# VoedingSCH.net
KiCad netlist of a schematic drawn in Altium Designer
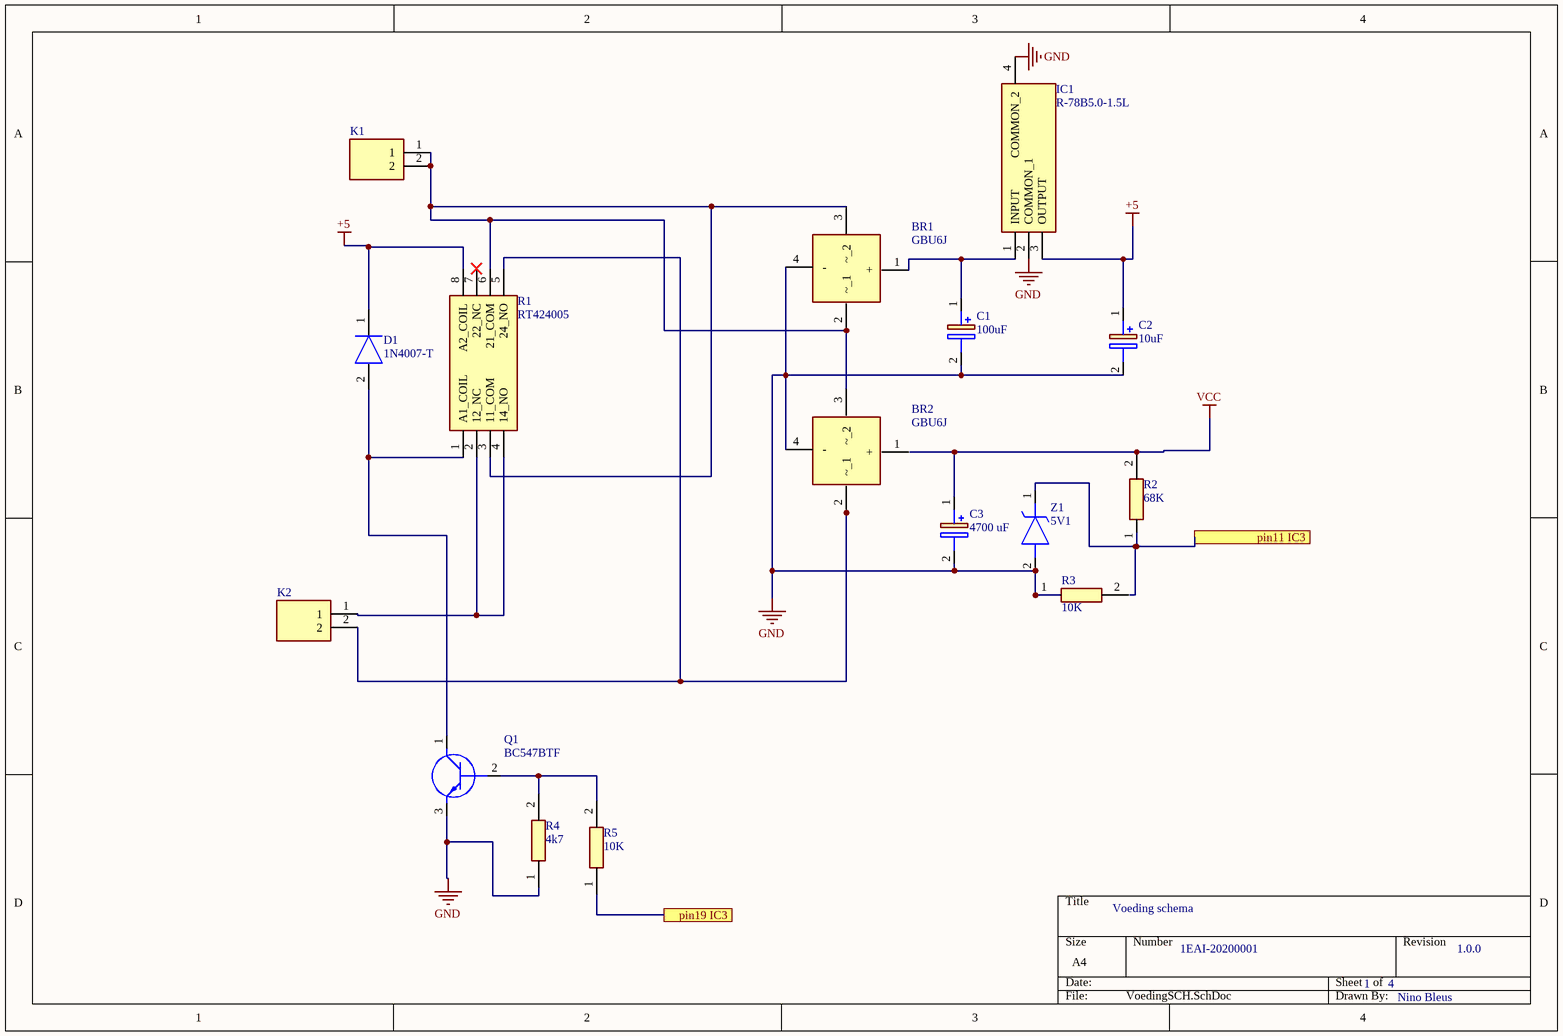
[diagram p0: VoedingSCH.SchDoc]

(export (version "E")
  (design (tool "Eeschema 10.0.6"))
  (components
    (comp (ref "BR1")
      (value "GBU6J")
      (footprint "SamacSys:GBU6J")
      (description "Bridge Rectifier")
      (libsource (lib "Schlib_soldeerbout") (part "GBU6J"))
    )
    (comp (ref "BR2")
      (value "GBU6J")
      (footprint "SamacSys:GBU6J")
      (description "Bridge Rectifier")
      (libsource (lib "Schlib_soldeerbout") (part "GBU6J"))
    )
    (comp (ref "C1")
      (value "100uF")
      (footprint "SamacSys:CAPPRD350W60D800H1250")
      (description "Capacitor Polarised")
      (fields (field (name "MANUFACTURER_PART_NUMBER") "ESK107M050AG3EA"))
      (libsource (lib "*") (part "ESK107M050AG3EA"))
    )
    (comp (ref "C2")
      (value "10uF")
      (footprint "SamacSys:CAPPRD250W45D630H850")
      (description "Capacitor Polarised")
      (fields (field (name "MANUFACTURER_PART_NUMBER") "ESS106M050AE2AA"))
      (libsource (lib "Schlib_soldeerbout") (part "10uF Capaciteit"))
    )
    (comp (ref "C3")
      (value "4700 uF")
      (footprint "SamacSys:CAPPRD1000W80D2200H3700")
      (description "Capacitor Polarised")
      (fields
        (field (name "MOUSER2 PART NUMBER") "80-ESK478M050AQ3AA")
        (field (name "MANUFACTURER_PART_NUMBER") "ESK478M050AQ3AA")
      )
      (libsource (lib "Schlib_soldeerbout") (part "4700 uF capaciteit"))
    )
    (comp (ref "D1")
      (value "1N4007-T")
      (footprint "SamacSys:DIOAD1408W86L464D236")
      (description "Diode")
      (fields (field (name "MOUSER2 PART NUMBER") "583-1N4007-T"))
      (libsource (lib "Schlib_soldeerbout") (part "1N4007-T"))
    )
    (comp (ref "IC1")
      (value "R-78B5.0-1.5L")
      (footprint "SamacSys:TL78005CKTTR")
      (description "Integrated Circuit")
      (fields (field (name "MANUFACTURER_PART_NUMBER") "TL780-05CKTTR"))
      (libsource (lib "*") (part "TL780-05CKTTR"))
    )
    (comp (ref "K1")
      (value "printkroonconnector")
      (footprint "SamacSys:1729128")
      (description "Connector")
      (fields (field (name "MANUFACTURER_PART_NUMBER") "1729128"))
      (libsource (lib "Schlib_soldeerbout") (part "printkroonconnector"))
    )
    (comp (ref "K2")
      (value "printkroonconnector")
      (footprint "SamacSys:1729128")
      (description "Connector")
      (fields (field (name "MANUFACTURER_PART_NUMBER") "1729128"))
      (libsource (lib "Schlib_soldeerbout") (part "printkroonconnector"))
    )
    (comp (ref "Q1")
      (value "BC547BTF")
      (footprint "SamacSys:BC33740TA")
      (description "Transistor BJT NPN")
      (libsource (lib "Schlib_soldeerbout") (part "BC547BTF"))
    )
    (comp (ref "R1")
      (value "RT424005")
      (footprint "SamacSys:RT42")
      (description "Relay or Contactor")
      (fields (field (name "MOUSER2 PART NUMBER") "655-RT424005"))
      (libsource (lib "Schlib_soldeerbout") (part "RT424005"))
    )
    (comp (ref "R2")
      (value "68K")
      (footprint "SamacSys:RESC2012X65N")
      (description "Resistor")
      (fields (field (name "MANUFACTURER_PART_NUMBER") "ESR10EZPJ183"))
      (libsource (lib "") (part "ESR10EZPJ183_1"))
    )
    (comp (ref "R3")
      (value "10K")
      (footprint "SamacSys:RESC2012X65N")
      (description "Resistor")
      (fields (field (name "MANUFACTURER_PART_NUMBER") "ESR10EZPJ183"))
      (libsource (lib "Schlib_soldeerbout") (part "ESR10EZPJ183"))
    )
    (comp (ref "R4")
      (value "4k7")
      (footprint "SamacSys:RESC2012X65N")
      (description "Resistor")
      (fields (field (name "MANUFACTURER_PART_NUMBER") "ESR10EZPJ183"))
      (libsource (lib "") (part "ESR10EZPJ183_1"))
    )
    (comp (ref "R5")
      (value "10K")
      (footprint "SamacSys:RESC2012X65N")
      (description "Resistor")
      (fields (field (name "MANUFACTURER_PART_NUMBER") "ESR10EZPJ183"))
      (libsource (lib "") (part "ESR10EZPJ183_1"))
    )
    (comp (ref "Z1")
      (value "5V1")
      (footprint "SamacSys:DIOAD1068W53L380D172")
      (description "Zener Diode")
      (fields (field (name "MANUFACTURER_PART_NUMBER") "1N5231B"))
      (libsource (lib "Schlib_soldeerbout") (part "1N5231B"))
    )
  )
  (nets
    (net (code "1") (name "+5") (class "Default")
      (node (ref "C2") (pin "1") (pinfunction "+_1") (pintype "passive"))
      (node (ref "D1") (pin "1") (pinfunction "K_1") (pintype "passive"))
      (node (ref "IC1") (pin "3") (pinfunction "OUTPUT_3") (pintype "passive"))
      (node (ref "R1") (pin "8") (pinfunction "A2_COIL_8") (pintype "passive"))
    )
    (net (code "2") (name "/pin11 IC3") (class "Default")
      (node (ref "R2") (pin "1") (pinfunction "1_1") (pintype "passive"))
      (node (ref "Z1") (pin "1") (pinfunction "K_1") (pintype "passive"))
    )
    (net (code "3") (name "/pin19 IC3") (class "Default")
      (node (ref "R5") (pin "1") (pinfunction "1_1") (pintype "passive"))
    )
    (net (code "4") (name "GND") (class "Default")
      (node (ref "BR1") (pin "4") (pinfunction "-_4") (pintype "passive"))
      (node (ref "BR2") (pin "4") (pinfunction "-_4") (pintype "passive"))
      (node (ref "C1") (pin "2") (pinfunction "-_2") (pintype "passive"))
      (node (ref "C2") (pin "2") (pinfunction "-_2") (pintype "passive"))
      (node (ref "C3") (pin "2") (pinfunction "-_2") (pintype "passive"))
      (node (ref "IC1") (pin "2") (pinfunction "COMMON_1_2") (pintype "passive"))
      (node (ref "IC1") (pin "4") (pinfunction "COMMON_2_4") (pintype "passive"))
      (node (ref "Q1") (pin "3") (pinfunction "E_3") (pintype "passive"))
      (node (ref "R3") (pin "1") (pinfunction "1_1") (pintype "passive"))
      (node (ref "R4") (pin "1") (pinfunction "1_1") (pintype "passive"))
      (node (ref "Z1") (pin "2") (pinfunction "A_2") (pintype "passive"))
    )
    (net (code "5") (name "Net-(BR1-+)") (class "Default")
      (node (ref "BR1") (pin "1") (pinfunction "+_1") (pintype "passive"))
      (node (ref "C1") (pin "1") (pinfunction "+_1") (pintype "passive"))
      (node (ref "IC1") (pin "1") (pinfunction "INPUT_1") (pintype "passive"))
    )
    (net (code "6") (name "Net-(BR1-~_1)") (class "Default")
      (node (ref "BR1") (pin "2") (pinfunction "~_1_2") (pintype "passive"))
      (node (ref "BR1") (pin "3") (pinfunction "~_2_3") (pintype "passive"))
      (node (ref "BR2") (pin "3") (pinfunction "~_2_3") (pintype "passive"))
      (node (ref "K1") (pin "1") (pinfunction "1_1") (pintype "passive"))
      (node (ref "K1") (pin "2") (pinfunction "2_2") (pintype "passive"))
      (node (ref "R1") (pin "3") (pinfunction "11_COM_3") (pintype "passive"))
      (node (ref "R1") (pin "6") (pinfunction "21_COM_6") (pintype "passive"))
    )
    (net (code "7") (name "Net-(BR2-~_1)") (class "Default")
      (node (ref "BR2") (pin "2") (pinfunction "~_1_2") (pintype "passive"))
      (node (ref "K2") (pin "2") (pinfunction "2_2") (pintype "passive"))
      (node (ref "R1") (pin "5") (pinfunction "24_NO_5") (pintype "passive"))
    )
    (net (code "8") (name "Net-(D1-A)") (class "Default")
      (node (ref "D1") (pin "2") (pinfunction "A_2") (pintype "passive"))
      (node (ref "Q1") (pin "1") (pinfunction "C_1") (pintype "passive"))
      (node (ref "R1") (pin "1") (pinfunction "A1_COIL_1") (pintype "passive"))
    )
    (net (code "9") (name "Net-(Q1-B)") (class "Default")
      (node (ref "Q1") (pin "2") (pinfunction "B_2") (pintype "passive"))
      (node (ref "R4") (pin "2") (pinfunction "2_2") (pintype "passive"))
      (node (ref "R5") (pin "2") (pinfunction "2_2") (pintype "passive"))
    )
    (net (code "10") (name "Net-(R1-12_NC)") (class "Default")
      (node (ref "K2") (pin "1") (pinfunction "1_1") (pintype "passive"))
      (node (ref "R1") (pin "2") (pinfunction "12_NC_2") (pintype "passive"))
      (node (ref "R1") (pin "4") (pinfunction "14_NO_4") (pintype "passive"))
    )
    (net (code "11") (name "VCC") (class "Default")
      (node (ref "C3") (pin "1") (pinfunction "+_1") (pintype "passive"))
      (node (ref "R2") (pin "2") (pinfunction "2_2") (pintype "passive"))
    )
    (net (code "12") (name "unconnected-(BR2-+-Pad1)") (class "Default")
      (node (ref "BR2") (pin "1") (pinfunction "+_1") (pintype "passive"))
    )
    (net (code "13") (name "unconnected-(R1-22_NC-Pad7)") (class "Default")
      (node (ref "R1") (pin "7") (pinfunction "22_NC_7") (pintype "passive+no_connect"))
    )
    (net (code "14") (name "unconnected-(R3-Pad2)") (class "Default")
      (node (ref "R3") (pin "2") (pinfunction "2_2") (pintype "passive"))
    )
  )
)
